# Mazzoleni.net
KiCad netlist of a schematic drawn in Altium Designer
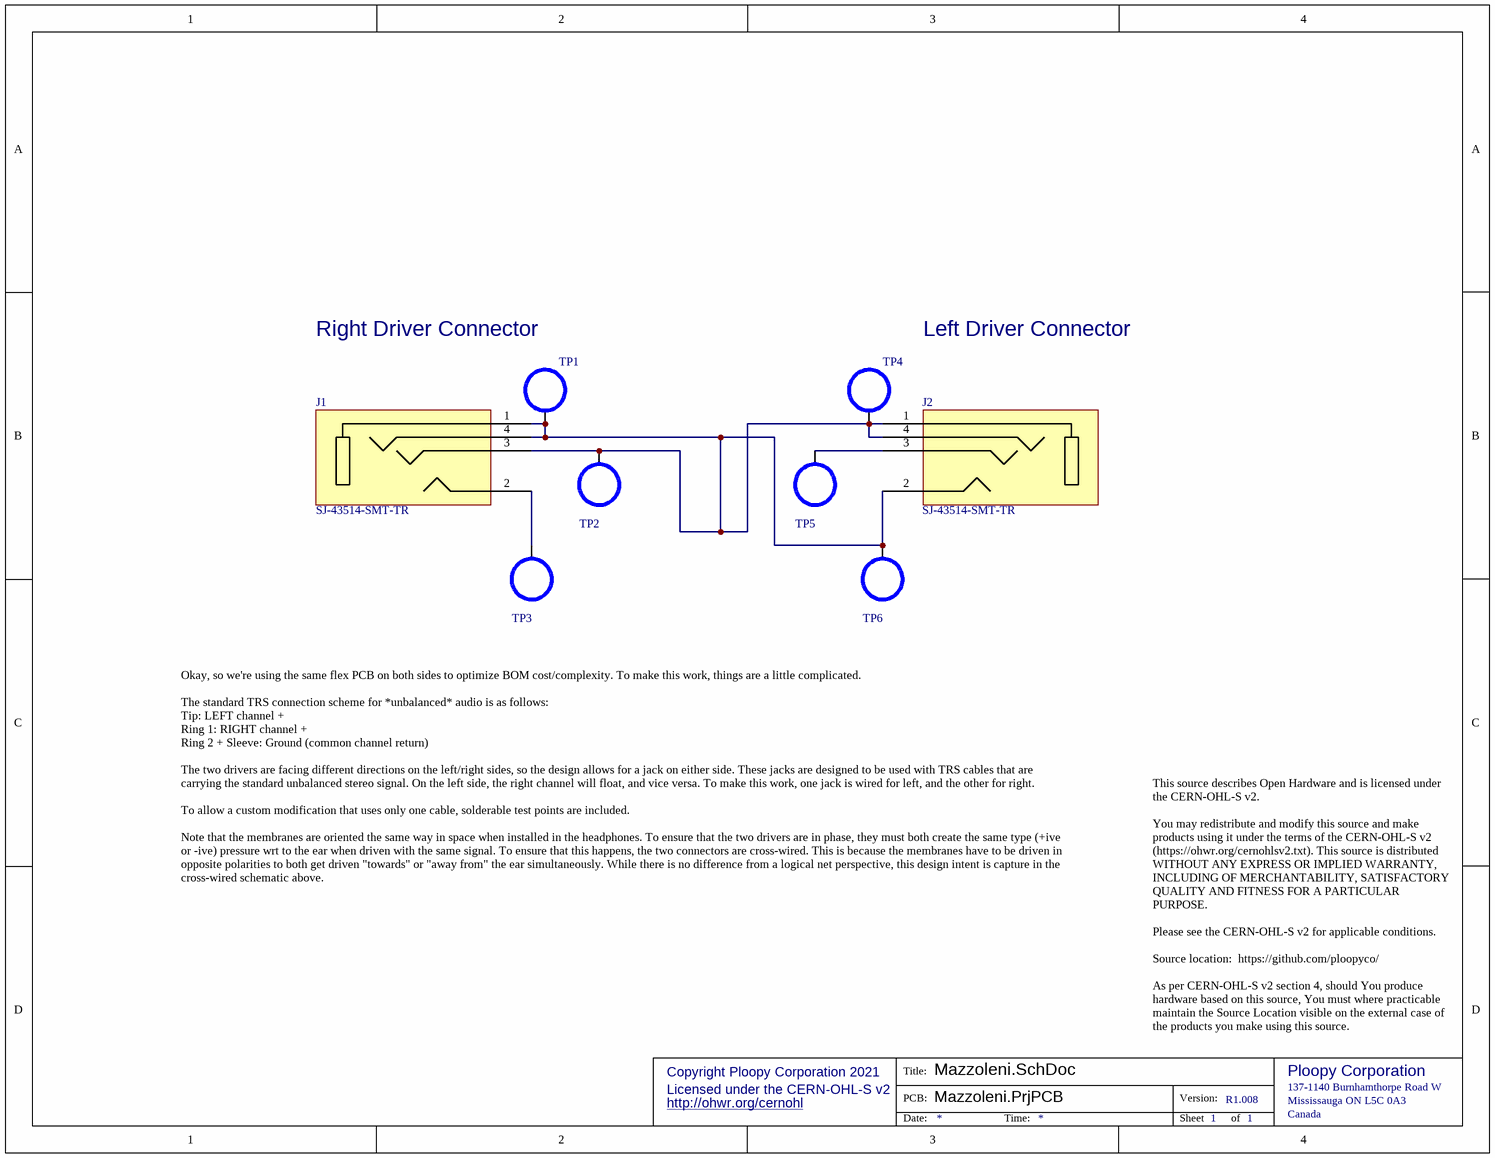
[diagram p0: Mazzoleni.SchDoc]

(export (version "E")
  (design (tool "Eeschema 10.0.6"))
  (components
    (comp (ref "J1")
      (value "SJ-43514-SMT-TR")
      (footprint "SJ-43514-SMT-TR")
      (libsource (lib "") (part "SJ-43514-SMT-TR_1"))
    )
    (comp (ref "J2")
      (value "SJ-43514-SMT-TR")
      (footprint "SJ-43514-SMT-TR")
      (libsource (lib "Connectors") (part "SJ-43514-SMT-TR"))
    )
    (comp (ref "TP1")
      (value "FlexSolderPad")
      (footprint "FlexSolderPad")
      (description "Pad designed for soldering a wire to a flex PCB. Reinforced for durability.")
      (libsource (lib "PCBFeatures") (part "FlexSolderPad"))
    )
    (comp (ref "TP2")
      (value "FlexSolderPad")
      (footprint "FlexSolderPad")
      (description "Pad designed for soldering a wire to a flex PCB. Reinforced for durability.")
      (libsource (lib "PCBFeatures") (part "FlexSolderPad"))
    )
    (comp (ref "TP3")
      (value "FlexSolderPad")
      (footprint "FlexSolderPad")
      (description "Pad designed for soldering a wire to a flex PCB. Reinforced for durability.")
      (libsource (lib "PCBFeatures") (part "FlexSolderPad"))
    )
    (comp (ref "TP4")
      (value "FlexSolderPad")
      (footprint "FlexSolderPad")
      (description "Pad designed for soldering a wire to a flex PCB. Reinforced for durability.")
      (libsource (lib "") (part "FlexSolderPad_1"))
    )
    (comp (ref "TP5")
      (value "FlexSolderPad")
      (footprint "FlexSolderPad")
      (description "Pad designed for soldering a wire to a flex PCB. Reinforced for durability.")
      (libsource (lib "") (part "FlexSolderPad_1"))
    )
    (comp (ref "TP6")
      (value "FlexSolderPad")
      (footprint "FlexSolderPad")
      (description "Pad designed for soldering a wire to a flex PCB. Reinforced for durability.")
      (libsource (lib "") (part "FlexSolderPad_1"))
    )
  )
  (nets
    (net (code "1") (name "Net-(J1-Pad1)") (class "Default")
      (node (ref "J1") (pin "1") (pinfunction "1_1") (pintype "passive"))
      (node (ref "J1") (pin "3") (pinfunction "3_3") (pintype "passive"))
      (node (ref "J1") (pin "4") (pinfunction "4_4") (pintype "passive"))
      (node (ref "J2") (pin "1") (pinfunction "1_1") (pintype "passive"))
      (node (ref "J2") (pin "2") (pinfunction "2_2") (pintype "passive"))
      (node (ref "J2") (pin "4") (pinfunction "4_4") (pintype "passive"))
      (node (ref "TP1") (pin "1") (pinfunction "1_1") (pintype "passive"))
      (node (ref "TP2") (pin "1") (pinfunction "1_1") (pintype "passive"))
      (node (ref "TP4") (pin "1") (pinfunction "1_1") (pintype "passive"))
      (node (ref "TP6") (pin "1") (pinfunction "1_1") (pintype "passive"))
    )
    (net (code "2") (name "Net-(J1-Pad2)") (class "Default")
      (node (ref "J1") (pin "2") (pinfunction "2_2") (pintype "passive"))
      (node (ref "TP3") (pin "1") (pinfunction "1_1") (pintype "passive"))
    )
    (net (code "3") (name "Net-(J2-Pad3)") (class "Default")
      (node (ref "J2") (pin "3") (pinfunction "3_3") (pintype "passive"))
      (node (ref "TP5") (pin "1") (pinfunction "1_1") (pintype "passive"))
    )
  )
)
